# 15pin_1mm_FPC.net
KiCad netlist of a schematic drawn in Altium Designer
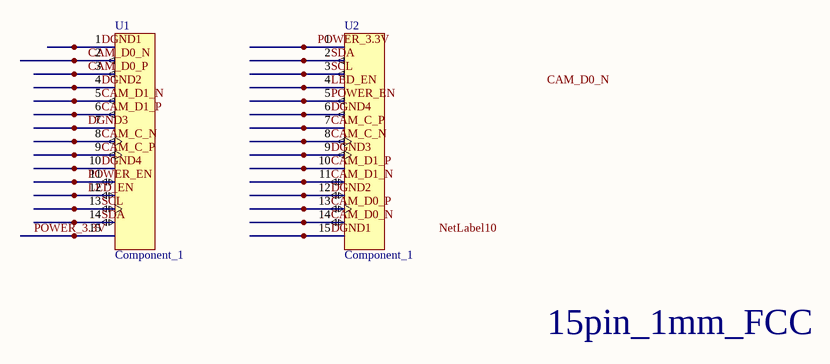
[diagram p0: 15pin_1mm_FPC.SchDoc]

(export (version "E")
  (design (tool "Eeschema 10.0.6"))
  (components
    (comp (ref "U1")
      (value "Component_1")
      (footprint "15pin_1mm_FPC")
      (libsource (lib "15pin_1mm_FPC_schematic") (part "Component_1"))
    )
    (comp (ref "U2")
      (value "Component_1")
      (footprint "15pin_1mm_FPC")
      (libsource (lib "15pin_1mm_FPC_schematic") (part "Component_1"))
    )
  )
  (nets
    (net (code "1") (name "/CAM_C_N") (class "Default")
      (node (ref "U1") (pin "8") (pintype "output"))
      (node (ref "U2") (pin "8") (pintype "output"))
    )
    (net (code "2") (name "/CAM_C_P") (class "Default")
      (node (ref "U1") (pin "9") (pintype "output"))
      (node (ref "U2") (pin "7") (pintype "power_in"))
    )
    (net (code "3") (name "/CAM_D0_N") (class "Default")
      (node (ref "U1") (pin "2") (pintype "output"))
      (node (ref "U2") (pin "14") (pintype "bidirectional"))
    )
    (net (code "4") (name "/CAM_D0_P") (class "Default")
      (node (ref "U1") (pin "3") (pintype "output"))
      (node (ref "U2") (pin "13") (pintype "bidirectional"))
    )
    (net (code "5") (name "/CAM_D1_N") (class "Default")
      (node (ref "U1") (pin "5") (pintype "output"))
      (node (ref "U2") (pin "11") (pintype "bidirectional"))
    )
    (net (code "6") (name "/CAM_D1_P") (class "Default")
      (node (ref "U1") (pin "6") (pintype "output"))
      (node (ref "U2") (pin "10") (pintype "power_in"))
    )
    (net (code "7") (name "/DGND1") (class "Default")
      (node (ref "U1") (pin "1") (pintype "power_in"))
      (node (ref "U2") (pin "15") (pintype "power_in"))
    )
    (net (code "8") (name "/DGND2") (class "Default")
      (node (ref "U1") (pin "4") (pintype "power_in"))
      (node (ref "U2") (pin "12") (pintype "bidirectional"))
    )
    (net (code "9") (name "/DGND3") (class "Default")
      (node (ref "U1") (pin "7") (pintype "power_in"))
      (node (ref "U2") (pin "9") (pintype "output"))
    )
    (net (code "10") (name "/DGND4") (class "Default")
      (node (ref "U1") (pin "10") (pintype "power_in"))
      (node (ref "U2") (pin "6") (pintype "output"))
    )
    (net (code "11") (name "/LED_EN") (class "Default")
      (node (ref "U1") (pin "12") (pintype "bidirectional"))
      (node (ref "U2") (pin "4") (pintype "power_in"))
    )
    (net (code "13") (name "/POWER_3.3V") (class "Default")
      (node (ref "U1") (pin "15") (pintype "power_in"))
      (node (ref "U2") (pin "1") (pintype "power_in"))
    )
    (net (code "14") (name "/POWER_EN") (class "Default")
      (node (ref "U1") (pin "11") (pintype "bidirectional"))
      (node (ref "U2") (pin "5") (pintype "output"))
    )
    (net (code "15") (name "/SCL") (class "Default")
      (node (ref "U1") (pin "13") (pintype "bidirectional"))
      (node (ref "U2") (pin "3") (pintype "output"))
    )
    (net (code "16") (name "/SDA") (class "Default")
      (node (ref "U1") (pin "14") (pintype "bidirectional"))
      (node (ref "U2") (pin "2") (pintype "output"))
    )
  )
)
